# XM-05_Typical_Application_Circuit.net
KiCad netlist of a schematic drawn in Altium Designer
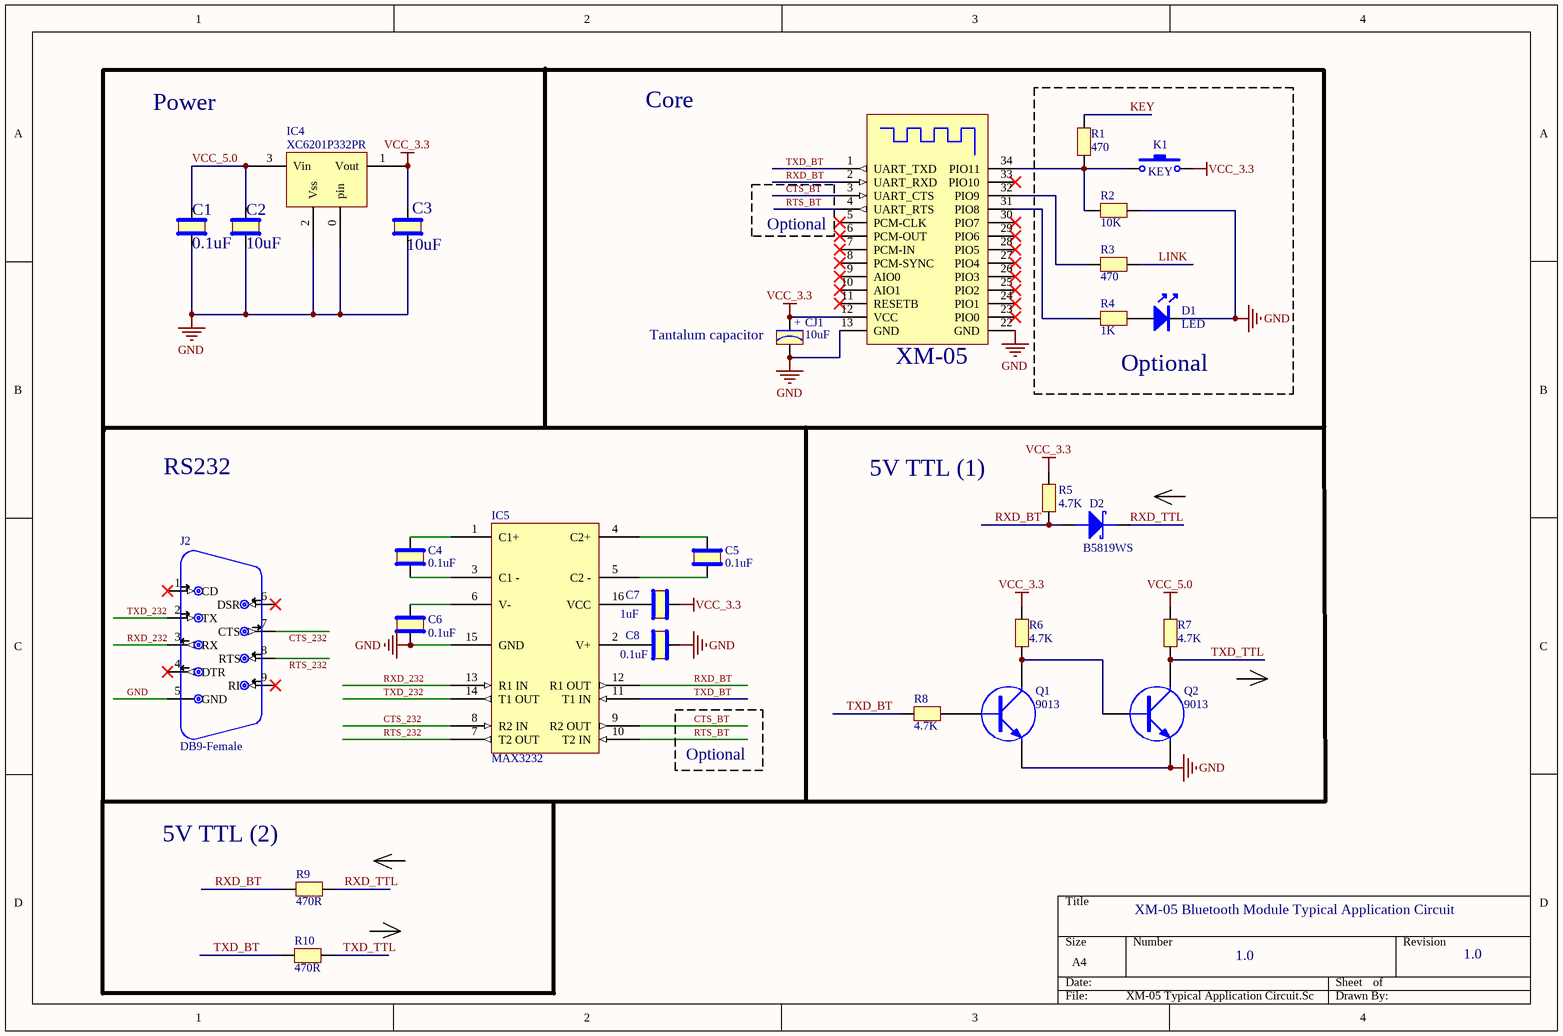
[diagram p0: XM-05 Typical Application Circuit.SchDoc]

(export (version "E")
  (design (tool "Eeschema 10.0.6"))
  (components
    (comp (ref "*1") (value "XM-05") (libsource (lib "wbh") (part "XM-101")))
    (comp (ref "C1") (value "0.1uF") (footprint "0603.RC") (libsource (lib "*") (part "CAP")))
    (comp (ref "C2") (value "10uF") (footprint "0603.RC") (libsource (lib "*") (part "CAP")))
    (comp (ref "C3") (value "10uF") (footprint "0603.RC") (libsource (lib "*") (part "CAP")))
    (comp (ref "C4") (value "0.1uF") (footprint "0603.RC") (libsource (lib "*") (part "CAP")))
    (comp (ref "C5") (value "0.1uF") (footprint "0603.RC") (libsource (lib "") (part "CAP_1")))
    (comp (ref "C6") (value "0.1uF") (footprint "0603.RC") (libsource (lib "*") (part "CAP")))
    (comp (ref "C7") (value "1uF") (footprint "0603.RC") (libsource (lib "") (part "CAP_2")))
    (comp (ref "C8") (value "0.1uF") (footprint "0603.RC") (libsource (lib "") (part "CAP_2")))
    (comp (ref "CJ1") (value "10uF") (footprint "1206.DC") (libsource (lib "wbh") (part "CAPJS")))
    (comp (ref "D1") (value "LED") (footprint "0603+") (libsource (lib "*") (part "LED")))
    (comp (ref "D2")
      (value "B5819WS")
      (footprint "SOD-323 - SMT")
      (description "Schottky Diode")
      (libsource (lib "wbh") (part "DIODE SCHOTTKY"))
    )
    (comp (ref "IC4") (value "XC6201P332PR") (footprint "SOT-89") (libsource (lib "*") (part "XC6201P301PR")))
    (comp (ref "IC5") (value "MAX3232") (footprint "SOP-16(N)") (libsource (lib "wbh") (part "MAX3232")))
    (comp (ref "J2") (value "DB9-Female") (footprint "DB9-F - 90") (libsource (lib "wbh") (part "DB9-F")))
    (comp (ref "K1") (value "KEY") (footprint "KEY-SS204") (libsource (lib "wbh") (part "SW-KEYSMT1")))
    (comp (ref "Q1")
      (value "9013")
      (footprint "SMT-SOT23MOS")
      (description "NPN Transistor")
      (libsource (lib "wbh") (part "NPN"))
    )
    (comp (ref "Q2")
      (value "9013")
      (footprint "SMT-SOT23MOS")
      (description "NPN Transistor")
      (libsource (lib "wbh") (part "NPN"))
    )
    (comp (ref "R1") (value "470") (footprint "0603.RC") (libsource (lib "wbh") (part "RES")))
    (comp (ref "R2") (value "10K") (footprint "0603.RC") (libsource (lib "") (part "RES_2")))
    (comp (ref "R3") (value "470") (footprint "0603.RC") (libsource (lib "") (part "RES_2")))
    (comp (ref "R4") (value "1K") (footprint "0603.RC") (libsource (lib "") (part "RES_2")))
    (comp (ref "R5") (value "4.7K") (footprint "0603.RC") (libsource (lib "wbh") (part "RES")))
    (comp (ref "R6") (value "4.7K") (footprint "0603.RC") (libsource (lib "") (part "RES_1")))
    (comp (ref "R7") (value "4.7K") (footprint "0603.RC") (libsource (lib "") (part "RES_1")))
    (comp (ref "R8") (value "4.7K") (footprint "0603.RC") (libsource (lib "") (part "RES_3")))
    (comp (ref "R9") (value "470R") (footprint "0603.RC") (libsource (lib "") (part "RES_3")))
    (comp (ref "R10") (value "470R") (footprint "0603.RC") (libsource (lib "") (part "RES_3")))
  )
  (nets
    (net (code "1") (name "/CTS_232") (class "Default")
      (node (ref "IC5") (pin "8") (pinfunction "R2_IN_8") (pintype "input"))
    )
    (net (code "2") (name "/CTS_BT") (class "Default")
      (node (ref "*1") (pin "3") (pinfunction "UART_CTS_3") (pintype "input"))
      (node (ref "IC5") (pin "9") (pinfunction "R2_OUT_9") (pintype "output"))
    )
    (net (code "3") (name "/KEY") (class "Default")
      (node (ref "R1") (pin "2") (pinfunction "2_2") (pintype "passive"))
    )
    (net (code "4") (name "/LINK") (class "Default")
      (node (ref "R3") (pin "1") (pinfunction "1_1") (pintype "passive"))
    )
    (net (code "5") (name "/RTS_232") (class "Default")
      (node (ref "IC5") (pin "7") (pinfunction "T2_OUT_7") (pintype "output"))
    )
    (net (code "6") (name "/RTS_BT") (class "Default")
      (node (ref "*1") (pin "4") (pinfunction "UART_RTS_4") (pintype "output"))
      (node (ref "IC5") (pin "10") (pinfunction "T2_IN_10") (pintype "input"))
    )
    (net (code "7") (name "/RXD_232") (class "Default")
      (node (ref "IC5") (pin "13") (pinfunction "R1_IN_13") (pintype "input"))
      (node (ref "J2") (pin "3") (pinfunction "RX_3") (pintype "output"))
    )
    (net (code "8") (name "/RXD_BT") (class "Default")
      (node (ref "*1") (pin "2") (pinfunction "UART_RXD_2") (pintype "input"))
      (node (ref "D2") (pin "1") (pinfunction "1_1") (pintype "passive"))
      (node (ref "IC5") (pin "12") (pinfunction "R1_OUT_12") (pintype "output"))
      (node (ref "R5") (pin "1") (pinfunction "1_1") (pintype "passive"))
      (node (ref "R9") (pin "2") (pinfunction "2_2") (pintype "passive"))
    )
    (net (code "9") (name "/RXD_TTL") (class "Default")
      (node (ref "D2") (pin "2") (pinfunction "2_2") (pintype "passive"))
      (node (ref "R9") (pin "1") (pinfunction "1_1") (pintype "passive"))
    )
    (net (code "10") (name "/TXD_232") (class "Default")
      (node (ref "IC5") (pin "14") (pinfunction "T1_OUT_14") (pintype "output"))
      (node (ref "J2") (pin "2") (pinfunction "TX_2") (pintype "input"))
    )
    (net (code "11") (name "/TXD_BT") (class "Default")
      (node (ref "*1") (pin "1") (pinfunction "UART_TXD_1") (pintype "output"))
      (node (ref "IC5") (pin "11") (pinfunction "T1_IN_11") (pintype "input"))
      (node (ref "R10") (pin "2") (pinfunction "2_2") (pintype "passive"))
      (node (ref "R8") (pin "2") (pinfunction "2_2") (pintype "passive"))
    )
    (net (code "12") (name "/TXD_TTL") (class "Default")
      (node (ref "Q2") (pin "D") (pinfunction "D_D") (pintype "passive"))
      (node (ref "R10") (pin "1") (pinfunction "1_1") (pintype "passive"))
      (node (ref "R7") (pin "1") (pinfunction "1_1") (pintype "passive"))
    )
    (net (code "13") (name "GND") (class "Default")
      (node (ref "*1") (pin "13") (pinfunction "GND_13") (pintype "passive"))
      (node (ref "*1") (pin "22") (pinfunction "GND_22") (pintype "passive"))
      (node (ref "C1") (pin "1") (pinfunction "1_1") (pintype "passive"))
      (node (ref "C2") (pin "1") (pinfunction "1_1") (pintype "passive"))
      (node (ref "C3") (pin "1") (pinfunction "1_1") (pintype "passive"))
      (node (ref "C6") (pin "1") (pinfunction "1_1") (pintype "passive"))
      (node (ref "C8") (pin "1") (pinfunction "1_1") (pintype "passive"))
      (node (ref "CJ1") (pin "K") (pinfunction "K_K") (pintype "passive"))
      (node (ref "D1") (pin "K") (pintype "passive"))
      (node (ref "IC4") (pin "0") (pinfunction "pin_0") (pintype "passive"))
      (node (ref "IC4") (pin "2") (pinfunction "Vss_2") (pintype "passive"))
      (node (ref "IC5") (pin "15") (pinfunction "GND_15") (pintype "power_in"))
      (node (ref "J2") (pin "5") (pinfunction "GND_5") (pintype "power_in"))
      (node (ref "Q1") (pin "S") (pinfunction "S_S") (pintype "passive"))
      (node (ref "Q2") (pin "S") (pinfunction "S_S") (pintype "passive"))
      (node (ref "R2") (pin "1") (pinfunction "1_1") (pintype "passive"))
    )
    (net (code "14") (name "Net-(*1-PIO8)") (class "Default")
      (node (ref "*1") (pin "31") (pinfunction "PIO8_31") (pintype "passive"))
      (node (ref "R4") (pin "2") (pinfunction "2_2") (pintype "passive"))
    )
    (net (code "15") (name "Net-(*1-PIO9)") (class "Default")
      (node (ref "*1") (pin "32") (pinfunction "PIO9_32") (pintype "passive"))
      (node (ref "R3") (pin "2") (pinfunction "2_2") (pintype "passive"))
    )
    (net (code "16") (name "Net-(*1-PIO11)") (class "Default")
      (node (ref "*1") (pin "34") (pinfunction "PIO11_34") (pintype "passive"))
      (node (ref "K1") (pin "2") (pinfunction "2_2") (pintype "passive"))
      (node (ref "R1") (pin "1") (pinfunction "1_1") (pintype "passive"))
      (node (ref "R2") (pin "2") (pinfunction "2_2") (pintype "passive"))
    )
    (net (code "17") (name "Net-(D1-PadA)") (class "Default")
      (node (ref "D1") (pin "A") (pintype "passive"))
      (node (ref "R4") (pin "1") (pinfunction "1_1") (pintype "passive"))
    )
    (net (code "18") (name "Net-(IC5-C1+)") (class "Default")
      (node (ref "C4") (pin "2") (pinfunction "2_2") (pintype "passive"))
      (node (ref "IC5") (pin "1") (pinfunction "C1+_1") (pintype "passive"))
    )
    (net (code "19") (name "Net-(IC5-C1_-)") (class "Default")
      (node (ref "C4") (pin "1") (pinfunction "1_1") (pintype "passive"))
      (node (ref "IC5") (pin "3") (pinfunction "C1_-_3") (pintype "passive"))
    )
    (net (code "20") (name "Net-(IC5-C2+)") (class "Default")
      (node (ref "C5") (pin "1") (pinfunction "1_1") (pintype "passive"))
      (node (ref "IC5") (pin "4") (pinfunction "C2+_4") (pintype "passive"))
    )
    (net (code "21") (name "Net-(IC5-C2_-)") (class "Default")
      (node (ref "C5") (pin "2") (pinfunction "2_2") (pintype "passive"))
      (node (ref "IC5") (pin "5") (pinfunction "C2_-_5") (pintype "passive"))
    )
    (net (code "22") (name "Net-(IC5-V+)") (class "Default")
      (node (ref "C8") (pin "2") (pinfunction "2_2") (pintype "passive"))
      (node (ref "IC5") (pin "2") (pinfunction "V+_2") (pintype "passive"))
    )
    (net (code "23") (name "Net-(IC5-V-)") (class "Default")
      (node (ref "C6") (pin "2") (pinfunction "2_2") (pintype "passive"))
      (node (ref "IC5") (pin "6") (pinfunction "V-_6") (pintype "power_in"))
    )
    (net (code "24") (name "Net-(IC5-VCC)") (class "Default")
      (node (ref "C7") (pin "2") (pinfunction "2_2") (pintype "passive"))
      (node (ref "IC5") (pin "16") (pinfunction "VCC_16") (pintype "power_in"))
    )
    (net (code "25") (name "Net-(Q1-PadD)") (class "Default")
      (node (ref "Q1") (pin "D") (pinfunction "D_D") (pintype "passive"))
      (node (ref "Q2") (pin "G") (pinfunction "G_G") (pintype "passive"))
      (node (ref "R6") (pin "1") (pinfunction "1_1") (pintype "passive"))
    )
    (net (code "26") (name "Net-(Q1-PadG)") (class "Default")
      (node (ref "Q1") (pin "G") (pinfunction "G_G") (pintype "passive"))
      (node (ref "R8") (pin "1") (pinfunction "1_1") (pintype "passive"))
    )
    (net (code "27") (name "VCC_3.3") (class "Default")
      (node (ref "*1") (pin "12") (pinfunction "VCC_12") (pintype "power_in"))
      (node (ref "C3") (pin "2") (pinfunction "2_2") (pintype "passive"))
      (node (ref "C7") (pin "1") (pinfunction "1_1") (pintype "passive"))
      (node (ref "CJ1") (pin "A") (pinfunction "A_A") (pintype "passive"))
      (node (ref "IC4") (pin "1") (pinfunction "Vout_1") (pintype "passive"))
      (node (ref "K1") (pin "1") (pinfunction "1_1") (pintype "passive"))
      (node (ref "R5") (pin "2") (pinfunction "2_2") (pintype "passive"))
      (node (ref "R6") (pin "2") (pinfunction "2_2") (pintype "passive"))
    )
    (net (code "28") (name "VCC_5.0") (class "Default")
      (node (ref "C1") (pin "2") (pinfunction "2_2") (pintype "passive"))
      (node (ref "C2") (pin "2") (pinfunction "2_2") (pintype "passive"))
      (node (ref "IC4") (pin "3") (pinfunction "Vin_3") (pintype "passive"))
      (node (ref "R7") (pin "2") (pinfunction "2_2") (pintype "passive"))
    )
    (net (code "29") (name "unconnected-(*1-AIO0-Pad9)") (class "Default")
      (node (ref "*1") (pin "9") (pinfunction "AIO0_9") (pintype "passive+no_connect"))
    )
    (net (code "30") (name "unconnected-(*1-AIO1-Pad10)") (class "Default")
      (node (ref "*1") (pin "10") (pinfunction "AIO1_10") (pintype "passive+no_connect"))
    )
    (net (code "31") (name "unconnected-(*1-PCM-CLK-Pad5)") (class "Default")
      (node (ref "*1") (pin "5") (pinfunction "PCM-CLK_5") (pintype "passive+no_connect"))
    )
    (net (code "32") (name "unconnected-(*1-PCM-IN-Pad7)") (class "Default")
      (node (ref "*1") (pin "7") (pinfunction "PCM-IN_7") (pintype "passive+no_connect"))
    )
    (net (code "33") (name "unconnected-(*1-PCM-OUT-Pad6)") (class "Default")
      (node (ref "*1") (pin "6") (pinfunction "PCM-OUT_6") (pintype "passive+no_connect"))
    )
    (net (code "34") (name "unconnected-(*1-PCM-SYNC-Pad8)") (class "Default")
      (node (ref "*1") (pin "8") (pinfunction "PCM-SYNC_8") (pintype "passive+no_connect"))
    )
    (net (code "35") (name "unconnected-(*1-PIO0-Pad23)") (class "Default")
      (node (ref "*1") (pin "23") (pinfunction "PIO0_23") (pintype "passive+no_connect"))
    )
    (net (code "36") (name "unconnected-(*1-PIO1-Pad24)") (class "Default")
      (node (ref "*1") (pin "24") (pinfunction "PIO1_24") (pintype "passive+no_connect"))
    )
    (net (code "37") (name "unconnected-(*1-PIO2-Pad25)") (class "Default")
      (node (ref "*1") (pin "25") (pinfunction "PIO2_25") (pintype "passive+no_connect"))
    )
    (net (code "38") (name "unconnected-(*1-PIO3-Pad26)") (class "Default")
      (node (ref "*1") (pin "26") (pinfunction "PIO3_26") (pintype "passive+no_connect"))
    )
    (net (code "39") (name "unconnected-(*1-PIO4-Pad27)") (class "Default")
      (node (ref "*1") (pin "27") (pinfunction "PIO4_27") (pintype "passive+no_connect"))
    )
    (net (code "40") (name "unconnected-(*1-PIO5-Pad28)") (class "Default")
      (node (ref "*1") (pin "28") (pinfunction "PIO5_28") (pintype "passive+no_connect"))
    )
    (net (code "41") (name "unconnected-(*1-PIO6-Pad29)") (class "Default")
      (node (ref "*1") (pin "29") (pinfunction "PIO6_29") (pintype "passive+no_connect"))
    )
    (net (code "42") (name "unconnected-(*1-PIO7-Pad30)") (class "Default")
      (node (ref "*1") (pin "30") (pinfunction "PIO7_30") (pintype "passive+no_connect"))
    )
    (net (code "43") (name "unconnected-(*1-PIO10-Pad33)") (class "Default")
      (node (ref "*1") (pin "33") (pinfunction "PIO10_33") (pintype "passive+no_connect"))
    )
    (net (code "44") (name "unconnected-(*1-RESETB-Pad11)") (class "Default")
      (node (ref "*1") (pin "11") (pinfunction "RESETB_11") (pintype "passive+no_connect"))
    )
    (net (code "45") (name "unconnected-(J2-CD-Pad1)") (class "Default")
      (node (ref "J2") (pin "1") (pinfunction "CD_1") (pintype "input+no_connect"))
    )
    (net (code "46") (name "unconnected-(J2-CTS-Pad7)") (class "Default")
      (node (ref "J2") (pin "7") (pinfunction "CTS_7") (pintype "output"))
    )
    (net (code "47") (name "unconnected-(J2-DSR-Pad6)") (class "Default")
      (node (ref "J2") (pin "6") (pinfunction "DSR_6") (pintype "input+no_connect"))
    )
    (net (code "48") (name "unconnected-(J2-DTR-Pad4)") (class "Default")
      (node (ref "J2") (pin "4") (pinfunction "DTR_4") (pintype "output+no_connect"))
    )
    (net (code "49") (name "unconnected-(J2-RI-Pad9)") (class "Default")
      (node (ref "J2") (pin "9") (pinfunction "RI_9") (pintype "input+no_connect"))
    )
    (net (code "50") (name "unconnected-(J2-RTS-Pad8)") (class "Default")
      (node (ref "J2") (pin "8") (pinfunction "RTS_8") (pintype "input"))
    )
  )
)
